# New_Project_2025-06-03_19-35-41.net
KiCad netlist of a schematic drawn in EasyEDA Pro
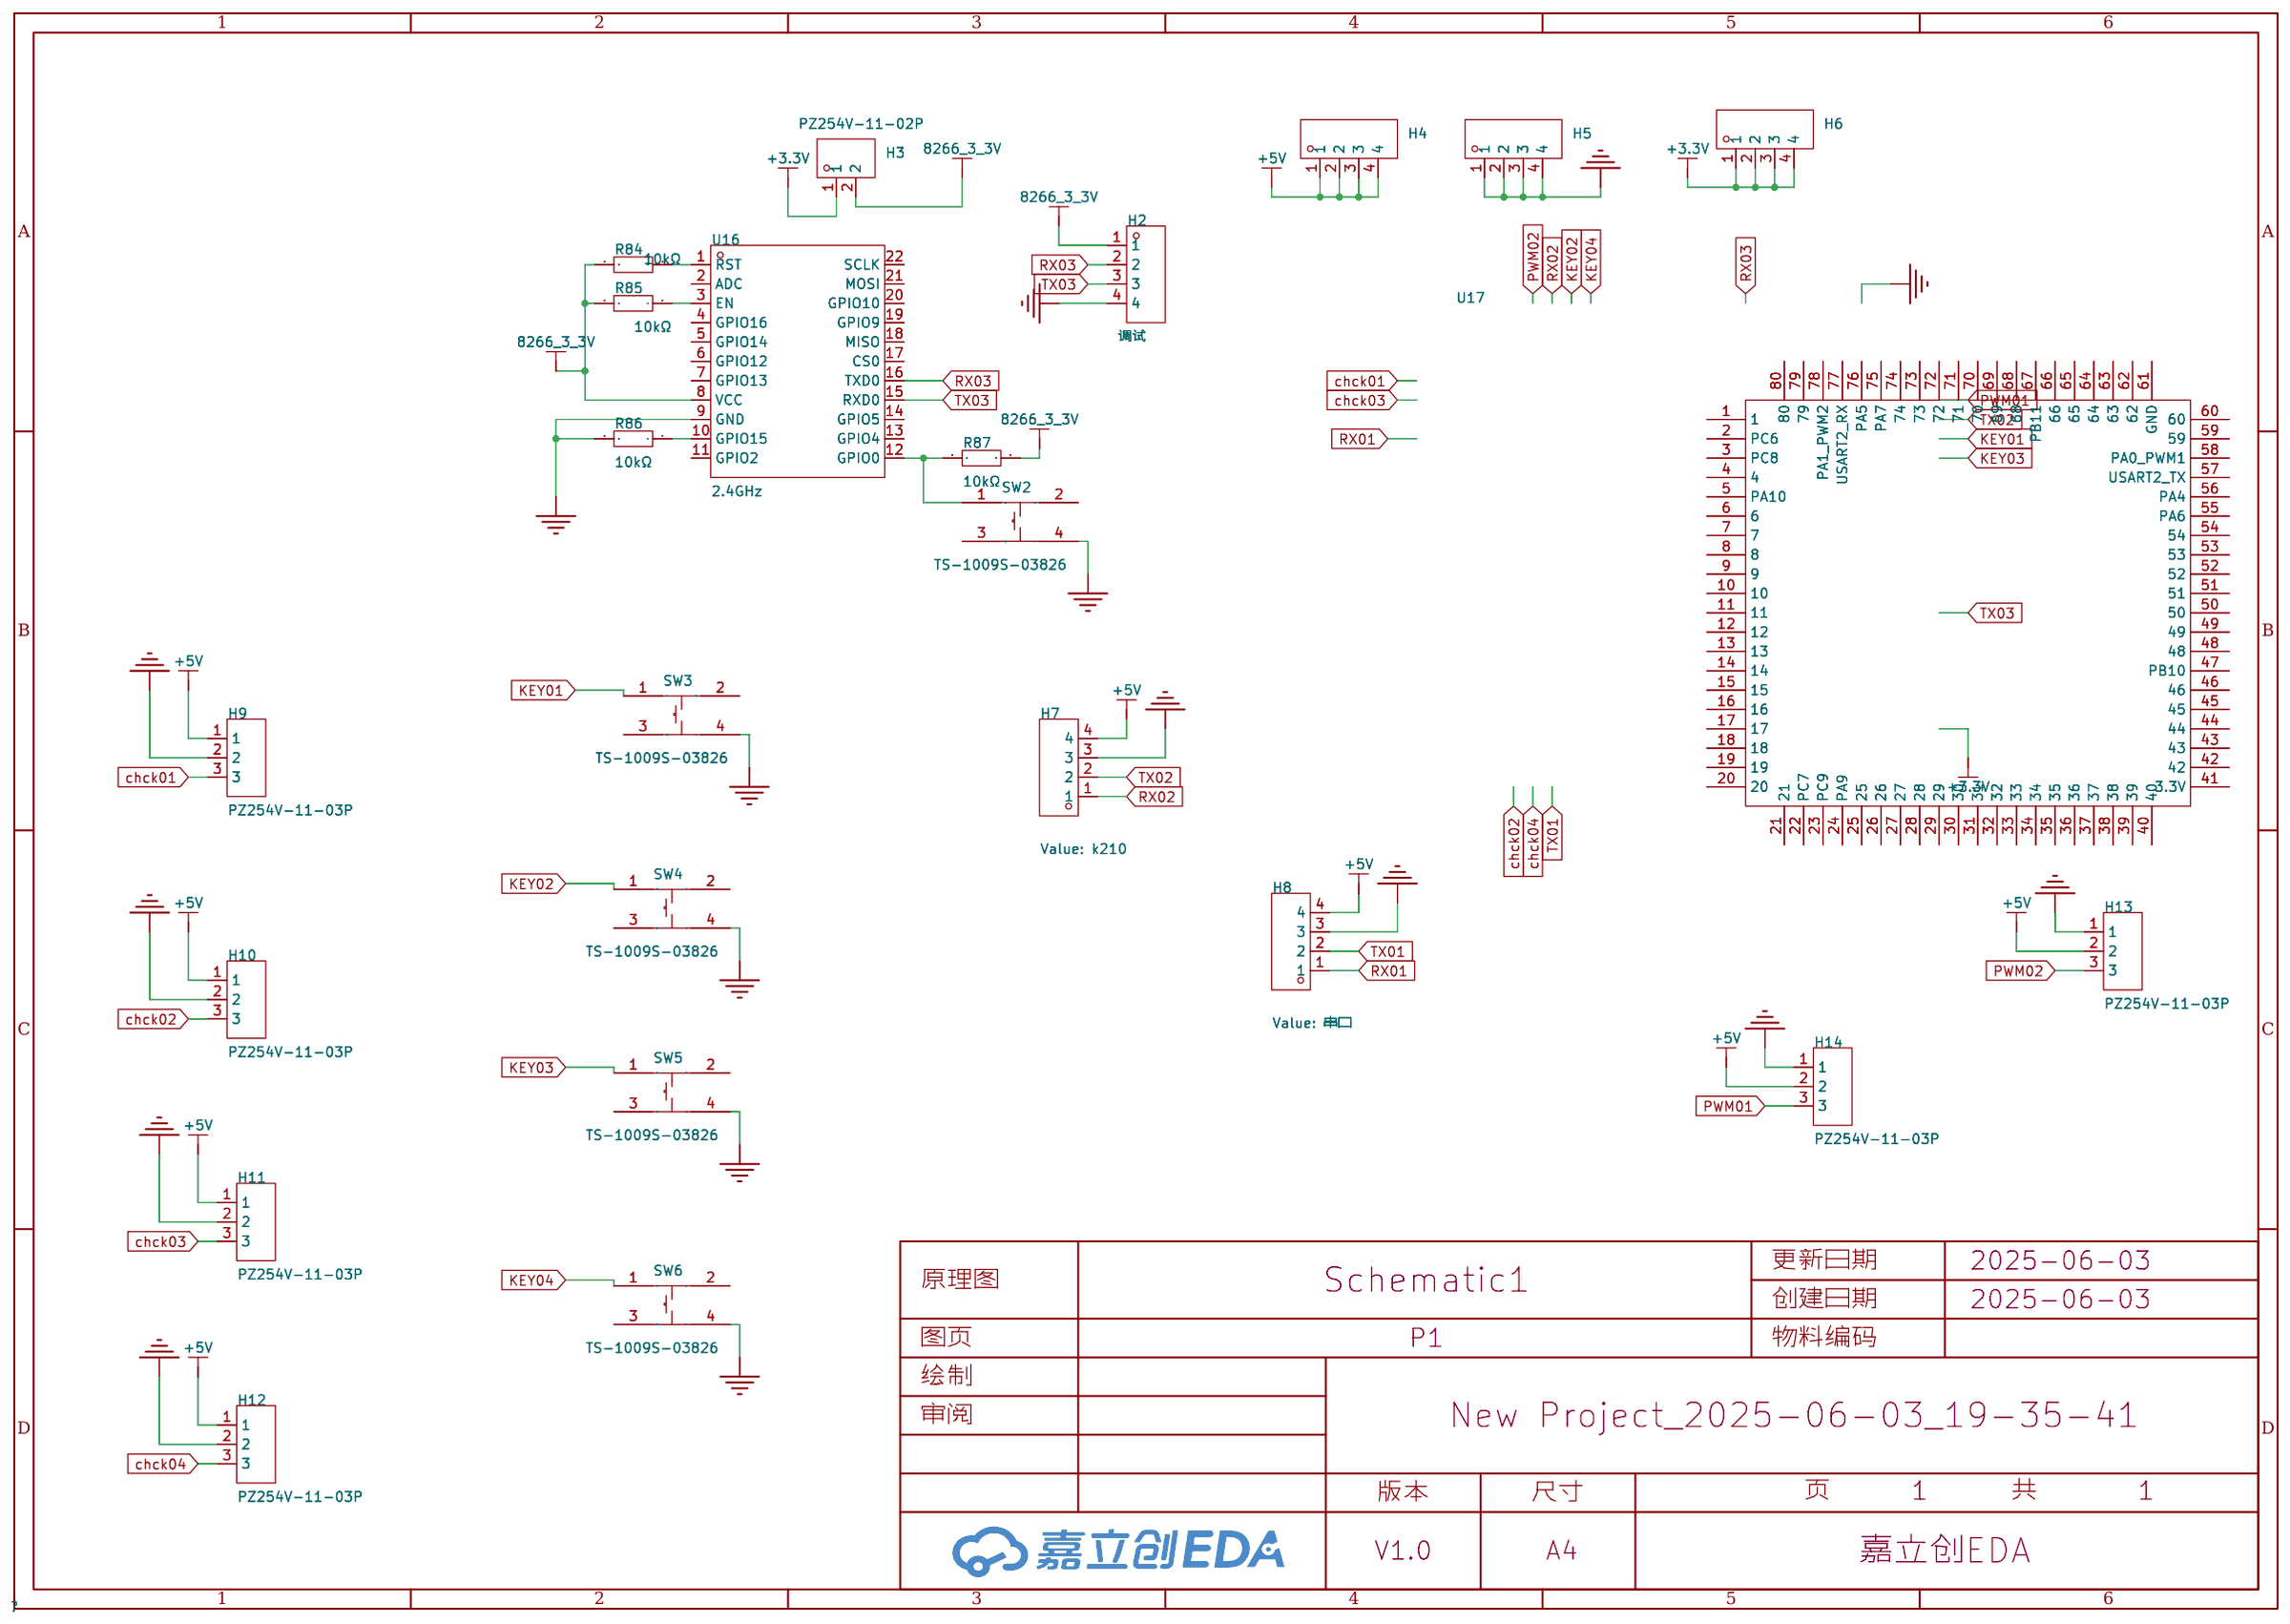
[diagram p0: schematic sheet]

(export (version "E")
  (design (tool "Eeschema 10.0.6"))
  (components
    (comp (ref "H2")
      (value "调试")
      (footprint "easyedapro:HDR-TH_4P-P2.54-V-M")
      (fields (field (name "Manufacturer") "XFCN(兴飞)"))
      (libsource (lib "easyedapro") (part "PZ254V-11-04P_C2691448"))
    )
    (comp (ref "H3")
      (value "PZ254V-11-02P")
      (footprint "easyedapro:HDR-TH_2P-P2.54-V-M")
      (fields (field (name "Manufacturer") "XFCN(兴飞)"))
      (libsource (lib "easyedapro") (part "PZ254V-11-02P"))
    )
    (comp (ref "H4")
      (value "PZ254V-11-04P")
      (footprint "easyedapro:HDR-TH_4P-P2.54-V-M")
      (fields (field (name "Manufacturer") "XFCN(兴飞)"))
      (libsource (lib "easyedapro") (part "PZ254V-11-04P_C2691448"))
    )
    (comp (ref "H5")
      (value "PZ254V-11-04P")
      (footprint "easyedapro:HDR-TH_4P-P2.54-V-M")
      (fields (field (name "Manufacturer") "XFCN(兴飞)"))
      (libsource (lib "easyedapro") (part "PZ254V-11-04P_C2691448"))
    )
    (comp (ref "H6")
      (value "PZ254V-11-04P")
      (footprint "easyedapro:HDR-TH_4P-P2.54-V-M")
      (fields (field (name "Manufacturer") "XFCN(兴飞)"))
      (libsource (lib "easyedapro") (part "PZ254V-11-04P_C2691448"))
    )
    (comp (ref "H7")
      (value "k210")
      (footprint "easyedapro:HDR-TH_4P-P2.54-V-M")
      (fields (field (name "Manufacturer") "XFCN(兴飞)"))
      (libsource (lib "easyedapro") (part "PZ254V-11-04P_C2691448"))
    )
    (comp (ref "H8")
      (value "串口")
      (footprint "easyedapro:HDR-TH_4P-P2.54-V-M")
      (fields (field (name "Manufacturer") "XFCN(兴飞)"))
      (libsource (lib "easyedapro") (part "PZ254V-11-04P_C2691448"))
    )
    (comp (ref "H9")
      (value "PZ254V-11-03P")
      (footprint "easyedapro:HDR-TH_3P-P2.54-V-M")
      (fields (field (name "Manufacturer") "XFCN(兴飞)"))
      (libsource (lib "easyedapro") (part "PZ254V-11-03P_C2937625"))
    )
    (comp (ref "H10")
      (value "PZ254V-11-03P")
      (footprint "easyedapro:HDR-TH_3P-P2.54-V-M")
      (fields (field (name "Manufacturer") "XFCN(兴飞)"))
      (libsource (lib "easyedapro") (part "PZ254V-11-03P_C2937625"))
    )
    (comp (ref "H11")
      (value "PZ254V-11-03P")
      (footprint "easyedapro:HDR-TH_3P-P2.54-V-M")
      (fields (field (name "Manufacturer") "XFCN(兴飞)"))
      (libsource (lib "easyedapro") (part "PZ254V-11-03P_C2937625"))
    )
    (comp (ref "H12")
      (value "PZ254V-11-03P")
      (footprint "easyedapro:HDR-TH_3P-P2.54-V-M")
      (fields (field (name "Manufacturer") "XFCN(兴飞)"))
      (libsource (lib "easyedapro") (part "PZ254V-11-03P_C2937625"))
    )
    (comp (ref "H13")
      (value "PZ254V-11-03P")
      (footprint "easyedapro:HDR-TH_3P-P2.54-V-M")
      (fields (field (name "Manufacturer") "XFCN(兴飞)"))
      (libsource (lib "easyedapro") (part "PZ254V-11-03P_C2937625"))
    )
    (comp (ref "H14")
      (value "PZ254V-11-03P")
      (footprint "easyedapro:HDR-TH_3P-P2.54-V-M")
      (fields (field (name "Manufacturer") "XFCN(兴飞)"))
      (libsource (lib "easyedapro") (part "PZ254V-11-03P_C2937625"))
    )
    (comp (ref "R84")
      (value "10kΩ")
      (fields (field (name "Manufacturer Part") "0603WAF1001T5E") (field (name "Manufacturer") "UniOhm"))
      (libsource (lib "easyedapro") (part "1kΩ"))
    )
    (comp (ref "R85")
      (value "10kΩ")
      (fields (field (name "Manufacturer Part") "0603WAF1001T5E") (field (name "Manufacturer") "UniOhm"))
      (libsource (lib "easyedapro") (part "1kΩ"))
    )
    (comp (ref "R86")
      (value "10kΩ")
      (fields (field (name "Manufacturer Part") "0603WAF1001T5E") (field (name "Manufacturer") "UniOhm"))
      (libsource (lib "easyedapro") (part "1kΩ"))
    )
    (comp (ref "R87")
      (value "10kΩ")
      (fields (field (name "Manufacturer Part") "0603WAF1001T5E") (field (name "Manufacturer") "UniOhm"))
      (libsource (lib "easyedapro") (part "1kΩ"))
    )
    (comp (ref "SW2")
      (value "TS-1009S-03826")
      (footprint "easyedapro:SW-SMD_4P-L4.5-W4.5-P3.00-LS7.0")
      (description "电路结构:单刀单掷;按钮形状:圆形按钮;安装方式:立贴;开关长度:4.5mm;开关宽度:4.5mm;开关高度:3.8mm;触点电流:50mA;额定电压(DC):12V;带灯:-;机械寿命:-;")
      (fields (field (name "Manufacturer") "XUNPU(讯普)"))
      (libsource (lib "easyedapro") (part "TS-1009S-03826"))
    )
    (comp (ref "SW3")
      (value "TS-1009S-03826")
      (footprint "easyedapro:SW-SMD_4P-L4.5-W4.5-P3.00-LS7.0")
      (description "电路结构:单刀单掷;按钮形状:圆形按钮;安装方式:立贴;开关长度:4.5mm;开关宽度:4.5mm;开关高度:3.8mm;触点电流:50mA;额定电压(DC):12V;带灯:-;机械寿命:-;")
      (fields (field (name "Manufacturer") "XUNPU(讯普)"))
      (libsource (lib "easyedapro") (part "TS-1009S-03826"))
    )
    (comp (ref "SW4")
      (value "TS-1009S-03826")
      (footprint "easyedapro:SW-SMD_4P-L4.5-W4.5-P3.00-LS7.0")
      (description "电路结构:单刀单掷;按钮形状:圆形按钮;安装方式:立贴;开关长度:4.5mm;开关宽度:4.5mm;开关高度:3.8mm;触点电流:50mA;额定电压(DC):12V;带灯:-;机械寿命:-;")
      (fields (field (name "Manufacturer") "XUNPU(讯普)"))
      (libsource (lib "easyedapro") (part "TS-1009S-03826"))
    )
    (comp (ref "SW5")
      (value "TS-1009S-03826")
      (footprint "easyedapro:SW-SMD_4P-L4.5-W4.5-P3.00-LS7.0")
      (description "电路结构:单刀单掷;按钮形状:圆形按钮;安装方式:立贴;开关长度:4.5mm;开关宽度:4.5mm;开关高度:3.8mm;触点电流:50mA;额定电压(DC):12V;带灯:-;机械寿命:-;")
      (fields (field (name "Manufacturer") "XUNPU(讯普)"))
      (libsource (lib "easyedapro") (part "TS-1009S-03826"))
    )
    (comp (ref "SW6")
      (value "TS-1009S-03826")
      (footprint "easyedapro:SW-SMD_4P-L4.5-W4.5-P3.00-LS7.0")
      (description "电路结构:单刀单掷;按钮形状:圆形按钮;安装方式:立贴;开关长度:4.5mm;开关宽度:4.5mm;开关高度:3.8mm;触点电流:50mA;额定电压(DC):12V;带灯:-;机械寿命:-;")
      (fields (field (name "Manufacturer") "XUNPU(讯普)"))
      (libsource (lib "easyedapro") (part "TS-1009S-03826"))
    )
    (comp (ref "U16")
      (value "2.4GHz")
      (footprint "easyedapro:WIFIM-SMD_ESP-12F-ESP8266MOD")
      (description "核心处理器:ESP8266芯片;频率:2.4GHz;天线形式:板载PCB天线;发射功率:16dBm;接收灵敏度:-90dBm;")
      (fields
        (field (name "Manufacturer Part") "ESP-12F(ESP8266MOD)")
        (field (name "Manufacturer") "Ai-Thinker(安信可)")
      )
      (libsource (lib "easyedapro") (part "ESP-12F(ESP8266MOD)"))
    )
    (comp (ref "U17") (value "~") (libsource (lib "easyedapro") (part "stm32f407vgt6private")))
  )
  (nets
    (net (code "1") (name "+3.3V") (class "Default")
      (node (ref "H3") (pin "1") (pinfunction "1_1") (pintype "unspecified"))
      (node (ref "H6") (pin "1") (pinfunction "1_1") (pintype "unspecified"))
      (node (ref "H6") (pin "2") (pinfunction "2_2") (pintype "unspecified"))
      (node (ref "H6") (pin "3") (pinfunction "3_3") (pintype "unspecified"))
      (node (ref "H6") (pin "4") (pinfunction "4_4") (pintype "unspecified"))
    )
    (net (code "2") (name "+5V") (class "Default")
      (node (ref "H10") (pin "1") (pinfunction "1_1") (pintype "unspecified"))
      (node (ref "H11") (pin "1") (pinfunction "1_1") (pintype "unspecified"))
      (node (ref "H12") (pin "1") (pinfunction "1_1") (pintype "unspecified"))
      (node (ref "H13") (pin "2") (pinfunction "2_2") (pintype "unspecified"))
      (node (ref "H14") (pin "2") (pinfunction "2_2") (pintype "unspecified"))
      (node (ref "H4") (pin "1") (pinfunction "1_1") (pintype "unspecified"))
      (node (ref "H4") (pin "2") (pinfunction "2_2") (pintype "unspecified"))
      (node (ref "H4") (pin "3") (pinfunction "3_3") (pintype "unspecified"))
      (node (ref "H4") (pin "4") (pinfunction "4_4") (pintype "unspecified"))
      (node (ref "H7") (pin "4") (pinfunction "4_4") (pintype "unspecified"))
      (node (ref "H8") (pin "4") (pinfunction "4_4") (pintype "unspecified"))
      (node (ref "H9") (pin "1") (pinfunction "1_1") (pintype "unspecified"))
    )
    (net (code "3") (name "8266_3_3V") (class "Default")
      (node (ref "H2") (pin "1") (pinfunction "1_1") (pintype "unspecified"))
      (node (ref "H3") (pin "2") (pinfunction "2_2") (pintype "unspecified"))
      (node (ref "R84") (pin "2") (pinfunction "2_2") (pintype "input"))
      (node (ref "R85") (pin "2") (pinfunction "2_2") (pintype "input"))
      (node (ref "R87") (pin "1") (pinfunction "1_1") (pintype "input"))
      (node (ref "U16") (pin "8") (pinfunction "VCC_8") (pintype "unspecified"))
    )
    (net (code "4") (name "GND") (class "Default")
      (node (ref "H10") (pin "2") (pinfunction "2_2") (pintype "unspecified"))
      (node (ref "H11") (pin "2") (pinfunction "2_2") (pintype "unspecified"))
      (node (ref "H12") (pin "2") (pinfunction "2_2") (pintype "unspecified"))
      (node (ref "H13") (pin "1") (pinfunction "1_1") (pintype "unspecified"))
      (node (ref "H14") (pin "1") (pinfunction "1_1") (pintype "unspecified"))
      (node (ref "H2") (pin "4") (pinfunction "4_4") (pintype "unspecified"))
      (node (ref "H5") (pin "1") (pinfunction "1_1") (pintype "unspecified"))
      (node (ref "H5") (pin "2") (pinfunction "2_2") (pintype "unspecified"))
      (node (ref "H5") (pin "3") (pinfunction "3_3") (pintype "unspecified"))
      (node (ref "H5") (pin "4") (pinfunction "4_4") (pintype "unspecified"))
      (node (ref "H7") (pin "3") (pinfunction "3_3") (pintype "unspecified"))
      (node (ref "H8") (pin "3") (pinfunction "3_3") (pintype "unspecified"))
      (node (ref "H9") (pin "2") (pinfunction "2_2") (pintype "unspecified"))
      (node (ref "R86") (pin "2") (pinfunction "2_2") (pintype "input"))
      (node (ref "SW2") (pin "4") (pinfunction "4_4") (pintype "unspecified"))
      (node (ref "SW3") (pin "4") (pinfunction "4_4") (pintype "unspecified"))
      (node (ref "SW4") (pin "4") (pinfunction "4_4") (pintype "unspecified"))
      (node (ref "SW5") (pin "4") (pinfunction "4_4") (pintype "unspecified"))
      (node (ref "SW6") (pin "4") (pinfunction "4_4") (pintype "unspecified"))
      (node (ref "U16") (pin "9") (pinfunction "GND_9") (pintype "unspecified"))
    )
    (net (code "5") (name "KEY01") (class "Default")
      (node (ref "SW3") (pin "1") (pinfunction "1_1") (pintype "unspecified"))
    )
    (net (code "6") (name "KEY02") (class "Default")
      (node (ref "SW4") (pin "1") (pinfunction "1_1") (pintype "unspecified"))
    )
    (net (code "7") (name "KEY03") (class "Default")
      (node (ref "SW5") (pin "1") (pinfunction "1_1") (pintype "unspecified"))
    )
    (net (code "8") (name "KEY04") (class "Default")
      (node (ref "SW6") (pin "1") (pinfunction "1_1") (pintype "unspecified"))
    )
    (net (code "9") (name "Net-(U16-EN)") (class "Default")
      (node (ref "R85") (pin "1") (pinfunction "1_1") (pintype "input"))
      (node (ref "U16") (pin "3") (pinfunction "EN_3") (pintype "unspecified"))
    )
    (net (code "10") (name "Net-(U16-GPIO0)") (class "Default")
      (node (ref "R87") (pin "2") (pinfunction "2_2") (pintype "input"))
      (node (ref "SW2") (pin "1") (pinfunction "1_1") (pintype "unspecified"))
      (node (ref "U16") (pin "12") (pinfunction "GPIO0_12") (pintype "unspecified"))
    )
    (net (code "11") (name "Net-(U16-GPIO15)") (class "Default")
      (node (ref "R86") (pin "1") (pinfunction "1_1") (pintype "input"))
      (node (ref "U16") (pin "10") (pinfunction "GPIO15_10") (pintype "unspecified"))
    )
    (net (code "12") (name "Net-(U16-RST)") (class "Default")
      (node (ref "R84") (pin "1") (pinfunction "1_1") (pintype "input"))
      (node (ref "U16") (pin "1") (pinfunction "RST_1") (pintype "unspecified"))
    )
    (net (code "13") (name "PWM01") (class "Default")
      (node (ref "H14") (pin "3") (pinfunction "3_3") (pintype "unspecified"))
    )
    (net (code "14") (name "PWM02") (class "Default")
      (node (ref "H13") (pin "3") (pinfunction "3_3") (pintype "unspecified"))
    )
    (net (code "15") (name "RX01") (class "Default")
      (node (ref "H8") (pin "1") (pinfunction "1_1") (pintype "unspecified"))
    )
    (net (code "16") (name "RX02") (class "Default")
      (node (ref "H7") (pin "1") (pinfunction "1_1") (pintype "unspecified"))
    )
    (net (code "17") (name "RX03") (class "Default")
      (node (ref "H2") (pin "2") (pinfunction "2_2") (pintype "unspecified"))
      (node (ref "U16") (pin "16") (pinfunction "TXD0_16") (pintype "unspecified"))
    )
    (net (code "18") (name "TX01") (class "Default")
      (node (ref "H8") (pin "2") (pinfunction "2_2") (pintype "unspecified"))
    )
    (net (code "19") (name "TX02") (class "Default")
      (node (ref "H7") (pin "2") (pinfunction "2_2") (pintype "unspecified"))
    )
    (net (code "20") (name "TX03") (class "Default")
      (node (ref "H2") (pin "3") (pinfunction "3_3") (pintype "unspecified"))
      (node (ref "U16") (pin "15") (pinfunction "RXD0_15") (pintype "unspecified"))
    )
    (net (code "21") (name "chck01") (class "Default")
      (node (ref "H9") (pin "3") (pinfunction "3_3") (pintype "unspecified"))
    )
    (net (code "22") (name "chck02") (class "Default")
      (node (ref "H10") (pin "3") (pinfunction "3_3") (pintype "unspecified"))
    )
    (net (code "23") (name "chck03") (class "Default")
      (node (ref "H11") (pin "3") (pinfunction "3_3") (pintype "unspecified"))
    )
    (net (code "24") (name "chck04") (class "Default")
      (node (ref "H12") (pin "3") (pinfunction "3_3") (pintype "unspecified"))
    )
    (net (code "25") (name "unconnected-(SW2-Pad2)") (class "Default")
      (node (ref "SW2") (pin "2") (pinfunction "2_2") (pintype "unspecified"))
    )
    (net (code "26") (name "unconnected-(SW2-Pad3)") (class "Default")
      (node (ref "SW2") (pin "3") (pinfunction "3_3") (pintype "unspecified"))
    )
    (net (code "27") (name "unconnected-(SW3-Pad2)") (class "Default")
      (node (ref "SW3") (pin "2") (pinfunction "2_2") (pintype "unspecified"))
    )
    (net (code "28") (name "unconnected-(SW3-Pad3)") (class "Default")
      (node (ref "SW3") (pin "3") (pinfunction "3_3") (pintype "unspecified"))
    )
    (net (code "29") (name "unconnected-(SW4-Pad2)") (class "Default")
      (node (ref "SW4") (pin "2") (pinfunction "2_2") (pintype "unspecified"))
    )
    (net (code "30") (name "unconnected-(SW4-Pad3)") (class "Default")
      (node (ref "SW4") (pin "3") (pinfunction "3_3") (pintype "unspecified"))
    )
    (net (code "31") (name "unconnected-(SW5-Pad2)") (class "Default")
      (node (ref "SW5") (pin "2") (pinfunction "2_2") (pintype "unspecified"))
    )
    (net (code "32") (name "unconnected-(SW5-Pad3)") (class "Default")
      (node (ref "SW5") (pin "3") (pinfunction "3_3") (pintype "unspecified"))
    )
    (net (code "33") (name "unconnected-(SW6-Pad2)") (class "Default")
      (node (ref "SW6") (pin "2") (pinfunction "2_2") (pintype "unspecified"))
    )
    (net (code "34") (name "unconnected-(SW6-Pad3)") (class "Default")
      (node (ref "SW6") (pin "3") (pinfunction "3_3") (pintype "unspecified"))
    )
    (net (code "35") (name "unconnected-(U16-ADC-Pad2)") (class "Default")
      (node (ref "U16") (pin "2") (pinfunction "ADC_2") (pintype "unspecified"))
    )
    (net (code "36") (name "unconnected-(U16-CS0-Pad17)") (class "Default")
      (node (ref "U16") (pin "17") (pinfunction "CS0_17") (pintype "unspecified"))
    )
    (net (code "37") (name "unconnected-(U16-GPIO2-Pad11)") (class "Default")
      (node (ref "U16") (pin "11") (pinfunction "GPIO2_11") (pintype "unspecified"))
    )
    (net (code "38") (name "unconnected-(U16-GPIO4-Pad13)") (class "Default")
      (node (ref "U16") (pin "13") (pinfunction "GPIO4_13") (pintype "unspecified"))
    )
    (net (code "39") (name "unconnected-(U16-GPIO5-Pad14)") (class "Default")
      (node (ref "U16") (pin "14") (pinfunction "GPIO5_14") (pintype "unspecified"))
    )
    (net (code "40") (name "unconnected-(U16-GPIO9-Pad19)") (class "Default")
      (node (ref "U16") (pin "19") (pinfunction "GPIO9_19") (pintype "unspecified"))
    )
    (net (code "41") (name "unconnected-(U16-GPIO10-Pad20)") (class "Default")
      (node (ref "U16") (pin "20") (pinfunction "GPIO10_20") (pintype "unspecified"))
    )
    (net (code "42") (name "unconnected-(U16-GPIO12-Pad6)") (class "Default")
      (node (ref "U16") (pin "6") (pinfunction "GPIO12_6") (pintype "unspecified"))
    )
    (net (code "43") (name "unconnected-(U16-GPIO13-Pad7)") (class "Default")
      (node (ref "U16") (pin "7") (pinfunction "GPIO13_7") (pintype "unspecified"))
    )
    (net (code "44") (name "unconnected-(U16-GPIO14-Pad5)") (class "Default")
      (node (ref "U16") (pin "5") (pinfunction "GPIO14_5") (pintype "unspecified"))
    )
    (net (code "45") (name "unconnected-(U16-GPIO16-Pad4)") (class "Default")
      (node (ref "U16") (pin "4") (pinfunction "GPIO16_4") (pintype "unspecified"))
    )
    (net (code "46") (name "unconnected-(U16-MISO-Pad18)") (class "Default")
      (node (ref "U16") (pin "18") (pinfunction "MISO_18") (pintype "unspecified"))
    )
    (net (code "47") (name "unconnected-(U16-MOSI-Pad21)") (class "Default")
      (node (ref "U16") (pin "21") (pinfunction "MOSI_21") (pintype "unspecified"))
    )
    (net (code "48") (name "unconnected-(U16-SCLK-Pad22)") (class "Default")
      (node (ref "U16") (pin "22") (pinfunction "SCLK_22") (pintype "unspecified"))
    )
    (net (code "49") (name "unconnected-(U17-3.3V-Pad41)") (class "Default")
      (node (ref "U17") (pin "41") (pinfunction "3.3V_41") (pintype "input"))
    )
    (net (code "50") (name "unconnected-(U17-GND-Pad61)") (class "Default")
      (node (ref "U17") (pin "61") (pinfunction "GND_61") (pintype "input"))
    )
    (net (code "51") (name "unconnected-(U17-PA0_PWM1-Pad58)") (class "Default")
      (node (ref "U17") (pin "58") (pinfunction "PA0_PWM1_58") (pintype "input"))
    )
    (net (code "52") (name "unconnected-(U17-PA1_PWM2-Pad78)") (class "Default")
      (node (ref "U17") (pin "78") (pinfunction "PA1_PWM2_78") (pintype "input"))
    )
    (net (code "53") (name "unconnected-(U17-PA4-Pad56)") (class "Default")
      (node (ref "U17") (pin "56") (pinfunction "PA4_56") (pintype "input"))
    )
    (net (code "54") (name "unconnected-(U17-PA5-Pad76)") (class "Default")
      (node (ref "U17") (pin "76") (pinfunction "PA5_76") (pintype "input"))
    )
    (net (code "55") (name "unconnected-(U17-PA6-Pad55)") (class "Default")
      (node (ref "U17") (pin "55") (pinfunction "PA6_55") (pintype "input"))
    )
    (net (code "56") (name "unconnected-(U17-PA7-Pad75)") (class "Default")
      (node (ref "U17") (pin "75") (pinfunction "PA7_75") (pintype "input"))
    )
    (net (code "57") (name "unconnected-(U17-PA9-Pad24)") (class "Default")
      (node (ref "U17") (pin "24") (pinfunction "PA9_24") (pintype "input"))
    )
    (net (code "58") (name "unconnected-(U17-PA10-Pad5)") (class "Default")
      (node (ref "U17") (pin "5") (pinfunction "PA10_5") (pintype "input"))
    )
    (net (code "59") (name "unconnected-(U17-PB10-Pad47)") (class "Default")
      (node (ref "U17") (pin "47") (pinfunction "PB10_47") (pintype "input"))
    )
    (net (code "60") (name "unconnected-(U17-PB11-Pad67)") (class "Default")
      (node (ref "U17") (pin "67") (pinfunction "PB11_67") (pintype "input"))
    )
    (net (code "61") (name "unconnected-(U17-PC6-Pad2)") (class "Default")
      (node (ref "U17") (pin "2") (pinfunction "PC6_2") (pintype "input"))
    )
    (net (code "62") (name "unconnected-(U17-PC7-Pad22)") (class "Default")
      (node (ref "U17") (pin "22") (pinfunction "PC7_22") (pintype "input"))
    )
    (net (code "63") (name "unconnected-(U17-PC8-Pad3)") (class "Default")
      (node (ref "U17") (pin "3") (pinfunction "PC8_3") (pintype "input"))
    )
    (net (code "64") (name "unconnected-(U17-PC9-Pad23)") (class "Default")
      (node (ref "U17") (pin "23") (pinfunction "PC9_23") (pintype "input"))
    )
    (net (code "65") (name "unconnected-(U17-Pad1)") (class "Default")
      (node (ref "U17") (pin "1") (pinfunction "1_1") (pintype "input"))
    )
    (net (code "66") (name "unconnected-(U17-Pad4)") (class "Default")
      (node (ref "U17") (pin "4") (pinfunction "4_4") (pintype "input"))
    )
    (net (code "67") (name "unconnected-(U17-Pad6)") (class "Default")
      (node (ref "U17") (pin "6") (pinfunction "6_6") (pintype "input"))
    )
    (net (code "68") (name "unconnected-(U17-Pad7)") (class "Default")
      (node (ref "U17") (pin "7") (pinfunction "7_7") (pintype "input"))
    )
    (net (code "69") (name "unconnected-(U17-Pad8)") (class "Default")
      (node (ref "U17") (pin "8") (pinfunction "8_8") (pintype "input"))
    )
    (net (code "70") (name "unconnected-(U17-Pad9)") (class "Default")
      (node (ref "U17") (pin "9") (pinfunction "9_9") (pintype "input"))
    )
    (net (code "71") (name "unconnected-(U17-Pad10)") (class "Default")
      (node (ref "U17") (pin "10") (pinfunction "10_10") (pintype "input"))
    )
    (net (code "72") (name "unconnected-(U17-Pad11)") (class "Default")
      (node (ref "U17") (pin "11") (pinfunction "11_11") (pintype "input"))
    )
    (net (code "73") (name "unconnected-(U17-Pad12)") (class "Default")
      (node (ref "U17") (pin "12") (pinfunction "12_12") (pintype "input"))
    )
    (net (code "74") (name "unconnected-(U17-Pad13)") (class "Default")
      (node (ref "U17") (pin "13") (pinfunction "13_13") (pintype "input"))
    )
    (net (code "75") (name "unconnected-(U17-Pad14)") (class "Default")
      (node (ref "U17") (pin "14") (pinfunction "14_14") (pintype "input"))
    )
    (net (code "76") (name "unconnected-(U17-Pad15)") (class "Default")
      (node (ref "U17") (pin "15") (pinfunction "15_15") (pintype "input"))
    )
    (net (code "77") (name "unconnected-(U17-Pad16)") (class "Default")
      (node (ref "U17") (pin "16") (pinfunction "16_16") (pintype "input"))
    )
    (net (code "78") (name "unconnected-(U17-Pad17)") (class "Default")
      (node (ref "U17") (pin "17") (pinfunction "17_17") (pintype "input"))
    )
    (net (code "79") (name "unconnected-(U17-Pad18)") (class "Default")
      (node (ref "U17") (pin "18") (pinfunction "18_18") (pintype "input"))
    )
    (net (code "80") (name "unconnected-(U17-Pad19)") (class "Default")
      (node (ref "U17") (pin "19") (pinfunction "19_19") (pintype "input"))
    )
    (net (code "81") (name "unconnected-(U17-Pad20)") (class "Default")
      (node (ref "U17") (pin "20") (pinfunction "20_20") (pintype "input"))
    )
    (net (code "82") (name "unconnected-(U17-Pad21)") (class "Default")
      (node (ref "U17") (pin "21") (pinfunction "21_21") (pintype "input"))
    )
    (net (code "83") (name "unconnected-(U17-Pad25)") (class "Default")
      (node (ref "U17") (pin "25") (pinfunction "25_25") (pintype "input"))
    )
    (net (code "84") (name "unconnected-(U17-Pad26)") (class "Default")
      (node (ref "U17") (pin "26") (pinfunction "26_26") (pintype "input"))
    )
    (net (code "85") (name "unconnected-(U17-Pad27)") (class "Default")
      (node (ref "U17") (pin "27") (pinfunction "27_27") (pintype "input"))
    )
    (net (code "86") (name "unconnected-(U17-Pad28)") (class "Default")
      (node (ref "U17") (pin "28") (pinfunction "28_28") (pintype "input"))
    )
    (net (code "87") (name "unconnected-(U17-Pad29)") (class "Default")
      (node (ref "U17") (pin "29") (pinfunction "29_29") (pintype "input"))
    )
    (net (code "88") (name "unconnected-(U17-Pad30)") (class "Default")
      (node (ref "U17") (pin "30") (pinfunction "30_30") (pintype "input"))
    )
    (net (code "89") (name "unconnected-(U17-Pad31)") (class "Default")
      (node (ref "U17") (pin "31") (pinfunction "31_31") (pintype "input"))
    )
    (net (code "90") (name "unconnected-(U17-Pad32)") (class "Default")
      (node (ref "U17") (pin "32") (pinfunction "32_32") (pintype "input"))
    )
    (net (code "91") (name "unconnected-(U17-Pad33)") (class "Default")
      (node (ref "U17") (pin "33") (pinfunction "33_33") (pintype "input"))
    )
    (net (code "92") (name "unconnected-(U17-Pad34)") (class "Default")
      (node (ref "U17") (pin "34") (pinfunction "34_34") (pintype "input"))
    )
    (net (code "93") (name "unconnected-(U17-Pad35)") (class "Default")
      (node (ref "U17") (pin "35") (pinfunction "35_35") (pintype "input"))
    )
    (net (code "94") (name "unconnected-(U17-Pad36)") (class "Default")
      (node (ref "U17") (pin "36") (pinfunction "36_36") (pintype "input"))
    )
    (net (code "95") (name "unconnected-(U17-Pad37)") (class "Default")
      (node (ref "U17") (pin "37") (pinfunction "37_37") (pintype "input"))
    )
    (net (code "96") (name "unconnected-(U17-Pad38)") (class "Default")
      (node (ref "U17") (pin "38") (pinfunction "38_38") (pintype "input"))
    )
    (net (code "97") (name "unconnected-(U17-Pad39)") (class "Default")
      (node (ref "U17") (pin "39") (pinfunction "39_39") (pintype "input"))
    )
    (net (code "98") (name "unconnected-(U17-Pad40)") (class "Default")
      (node (ref "U17") (pin "40") (pinfunction "40_40") (pintype "input"))
    )
    (net (code "99") (name "unconnected-(U17-Pad42)") (class "Default")
      (node (ref "U17") (pin "42") (pinfunction "42_42") (pintype "input"))
    )
    (net (code "100") (name "unconnected-(U17-Pad43)") (class "Default")
      (node (ref "U17") (pin "43") (pinfunction "43_43") (pintype "input"))
    )
    (net (code "101") (name "unconnected-(U17-Pad44)") (class "Default")
      (node (ref "U17") (pin "44") (pinfunction "44_44") (pintype "input"))
    )
    (net (code "102") (name "unconnected-(U17-Pad45)") (class "Default")
      (node (ref "U17") (pin "45") (pinfunction "45_45") (pintype "input"))
    )
    (net (code "103") (name "unconnected-(U17-Pad46)") (class "Default")
      (node (ref "U17") (pin "46") (pinfunction "46_46") (pintype "input"))
    )
    (net (code "104") (name "unconnected-(U17-Pad48)") (class "Default")
      (node (ref "U17") (pin "48") (pinfunction "48_48") (pintype "input"))
    )
    (net (code "105") (name "unconnected-(U17-Pad49)") (class "Default")
      (node (ref "U17") (pin "49") (pinfunction "49_49") (pintype "input"))
    )
    (net (code "106") (name "unconnected-(U17-Pad50)") (class "Default")
      (node (ref "U17") (pin "50") (pinfunction "50_50") (pintype "input"))
    )
    (net (code "107") (name "unconnected-(U17-Pad51)") (class "Default")
      (node (ref "U17") (pin "51") (pinfunction "51_51") (pintype "input"))
    )
    (net (code "108") (name "unconnected-(U17-Pad52)") (class "Default")
      (node (ref "U17") (pin "52") (pinfunction "52_52") (pintype "input"))
    )
    (net (code "109") (name "unconnected-(U17-Pad53)") (class "Default")
      (node (ref "U17") (pin "53") (pinfunction "53_53") (pintype "input"))
    )
    (net (code "110") (name "unconnected-(U17-Pad54)") (class "Default")
      (node (ref "U17") (pin "54") (pinfunction "54_54") (pintype "input"))
    )
    (net (code "111") (name "unconnected-(U17-Pad59)") (class "Default")
      (node (ref "U17") (pin "59") (pinfunction "59_59") (pintype "input"))
    )
    (net (code "112") (name "unconnected-(U17-Pad60)") (class "Default")
      (node (ref "U17") (pin "60") (pinfunction "60_60") (pintype "input"))
    )
    (net (code "113") (name "unconnected-(U17-Pad62)") (class "Default")
      (node (ref "U17") (pin "62") (pinfunction "62_62") (pintype "input"))
    )
    (net (code "114") (name "unconnected-(U17-Pad63)") (class "Default")
      (node (ref "U17") (pin "63") (pinfunction "63_63") (pintype "input"))
    )
    (net (code "115") (name "unconnected-(U17-Pad64)") (class "Default")
      (node (ref "U17") (pin "64") (pinfunction "64_64") (pintype "input"))
    )
    (net (code "116") (name "unconnected-(U17-Pad65)") (class "Default")
      (node (ref "U17") (pin "65") (pinfunction "65_65") (pintype "input"))
    )
    (net (code "117") (name "unconnected-(U17-Pad66)") (class "Default")
      (node (ref "U17") (pin "66") (pinfunction "66_66") (pintype "input"))
    )
    (net (code "118") (name "unconnected-(U17-Pad68)") (class "Default")
      (node (ref "U17") (pin "68") (pinfunction "68_68") (pintype "input"))
    )
    (net (code "119") (name "unconnected-(U17-Pad69)") (class "Default")
      (node (ref "U17") (pin "69") (pinfunction "69_69") (pintype "input"))
    )
    (net (code "120") (name "unconnected-(U17-Pad70)") (class "Default")
      (node (ref "U17") (pin "70") (pinfunction "70_70") (pintype "input"))
    )
    (net (code "121") (name "unconnected-(U17-Pad71)") (class "Default")
      (node (ref "U17") (pin "71") (pinfunction "71_71") (pintype "input"))
    )
    (net (code "122") (name "unconnected-(U17-Pad72)") (class "Default")
      (node (ref "U17") (pin "72") (pinfunction "72_72") (pintype "input"))
    )
    (net (code "123") (name "unconnected-(U17-Pad73)") (class "Default")
      (node (ref "U17") (pin "73") (pinfunction "73_73") (pintype "input"))
    )
    (net (code "124") (name "unconnected-(U17-Pad74)") (class "Default")
      (node (ref "U17") (pin "74") (pinfunction "74_74") (pintype "input"))
    )
    (net (code "125") (name "unconnected-(U17-Pad79)") (class "Default")
      (node (ref "U17") (pin "79") (pinfunction "79_79") (pintype "input"))
    )
    (net (code "126") (name "unconnected-(U17-Pad80)") (class "Default")
      (node (ref "U17") (pin "80") (pinfunction "80_80") (pintype "input"))
    )
    (net (code "127") (name "unconnected-(U17-USART2_RX-Pad77)") (class "Default")
      (node (ref "U17") (pin "77") (pinfunction "USART2_RX_77") (pintype "input"))
    )
    (net (code "128") (name "unconnected-(U17-USART2_TX-Pad57)") (class "Default")
      (node (ref "U17") (pin "57") (pinfunction "USART2_TX_57") (pintype "input"))
    )
  )
)
